# LED_Bar_Graph_Voltage_Display.net
KiCad netlist of a schematic drawn in Altium Designer
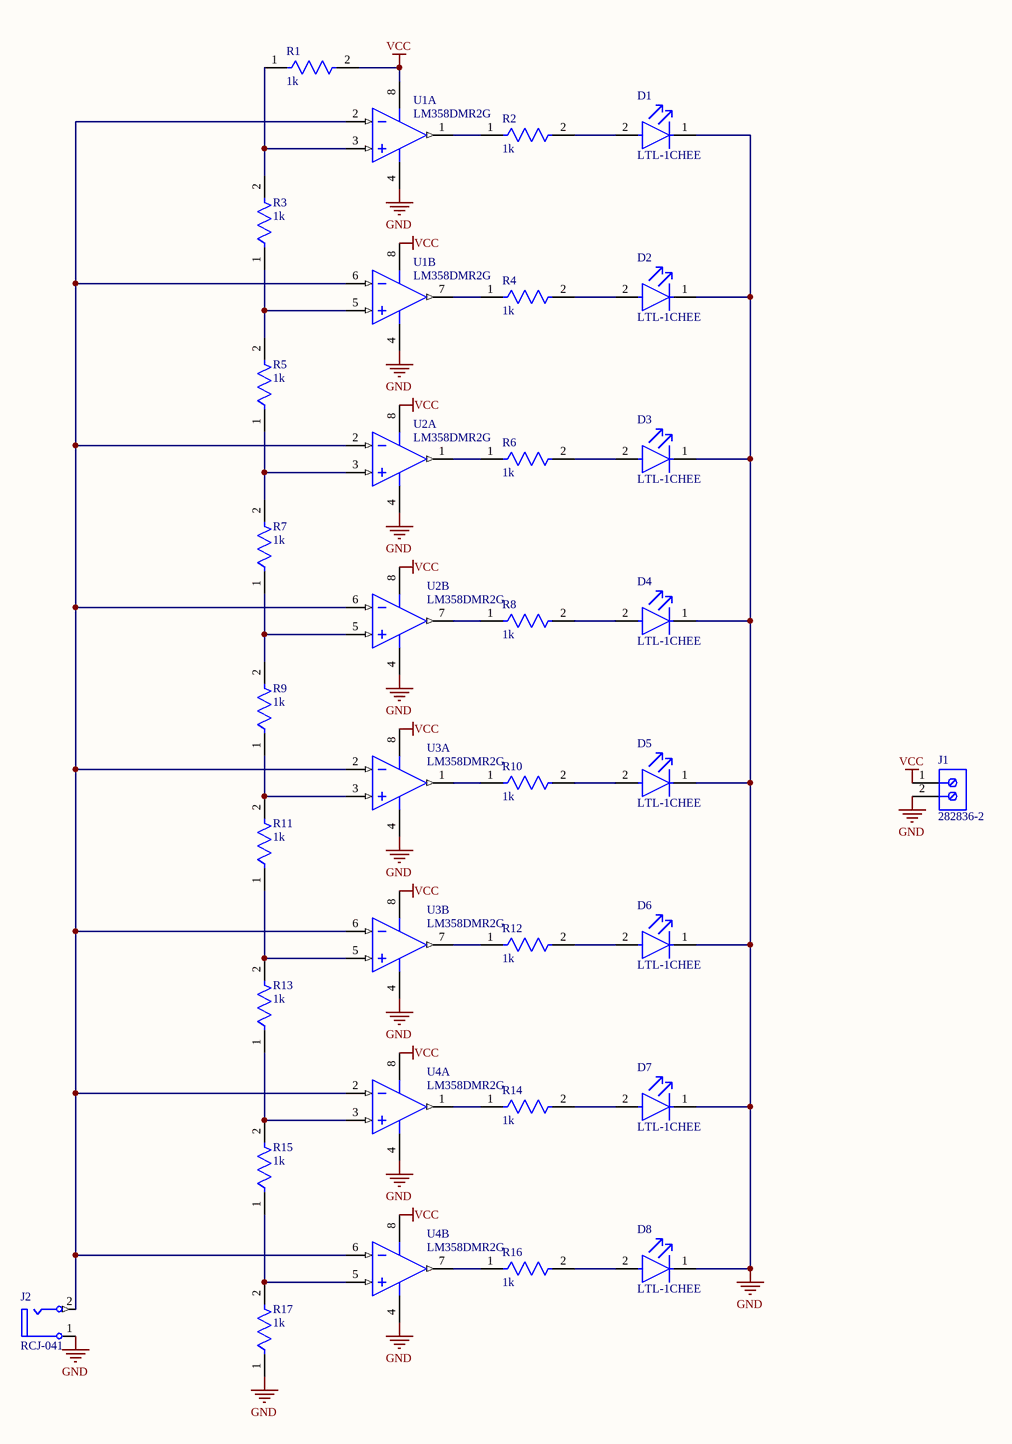
[diagram p0: LED Bar Graph Voltage Display.SchDoc]

(export (version "E")
  (design (tool "Eeschema 10.0.6"))
  (components
    (comp (ref "D1")
      (value "LTL-1CHEE")
      (footprint "FP-LTL-1CHEE-MFG")
      (description "LED RED CLEAR T/H")
      (libsource (lib "Altium Content Vault") (part "8706943c75ba83719d021d2fdc84c58"))
    )
    (comp (ref "D2")
      (value "LTL-1CHEE")
      (footprint "FP-LTL-1CHEE-MFG")
      (description "LED RED CLEAR T/H")
      (libsource (lib "Altium Content Vault") (part "8706943c75ba83719d021d2fdc84c58"))
    )
    (comp (ref "D3")
      (value "LTL-1CHEE")
      (footprint "FP-LTL-1CHEE-MFG")
      (description "LED RED CLEAR T/H")
      (libsource (lib "Altium Content Vault") (part "8706943c75ba83719d021d2fdc84c58"))
    )
    (comp (ref "D4")
      (value "LTL-1CHEE")
      (footprint "FP-LTL-1CHEE-MFG")
      (description "LED RED CLEAR T/H")
      (libsource (lib "Altium Content Vault") (part "8706943c75ba83719d021d2fdc84c58"))
    )
    (comp (ref "D5")
      (value "LTL-1CHEE")
      (footprint "FP-LTL-1CHEE-MFG")
      (description "LED RED CLEAR T/H")
      (libsource (lib "Altium Content Vault") (part "8706943c75ba83719d021d2fdc84c58"))
    )
    (comp (ref "D6")
      (value "LTL-1CHEE")
      (footprint "FP-LTL-1CHEE-MFG")
      (description "LED RED CLEAR T/H")
      (libsource (lib "Altium Content Vault") (part "8706943c75ba83719d021d2fdc84c58"))
    )
    (comp (ref "D7")
      (value "LTL-1CHEE")
      (footprint "FP-LTL-1CHEE-MFG")
      (description "LED RED CLEAR T/H")
      (libsource (lib "Altium Content Vault") (part "8706943c75ba83719d021d2fdc84c58"))
    )
    (comp (ref "D8")
      (value "LTL-1CHEE")
      (footprint "FP-LTL-1CHEE-MFG")
      (description "LED RED CLEAR T/H")
      (libsource (lib "Altium Content Vault") (part "8706943c75ba83719d021d2fdc84c58"))
    )
    (comp (ref "J1")
      (value "282836-2")
      (footprint "TECO-282836-2_V")
      (description "Female Header, Pitch 5 mm, 1 x 2 Position, Height 10 mm, Tail Length 3.5 mm, Rohs, Bulk")
      (fields (field (name "VOLTAGE") "300V") (field (name "MANUFACTURER") "TE Connectivity"))
      (libsource (lib "Altium Content Vault") (part "CN-1P-F-TB2"))
    )
    (comp (ref "J2")
      (value "RCJ-041")
      (footprint "CUI-RCJ-041_V")
      (description "Female RCJ Jack, 2 Position, Height 11.724 mm, Tail Length 4 mm, RoHS, Bulk")
      (libsource (lib "Altium Content Vault") (part "JACK-2CD2"))
    )
    (comp (ref "R1")
      (value "1k")
      (footprint "FP-CF14-MFG")
      (description "RES 7.5K OHM 1/4W 5% AXIAL")
      (fields (field (name "TOLERANCE") "5%"))
      (libsource (lib "Altium Content Vault") (part "1029c3af85768c4190bb7ad29bc67b5"))
    )
    (comp (ref "R2")
      (value "1k")
      (footprint "FP-CF14-MFG")
      (description "RES 7.5K OHM 1/4W 5% AXIAL")
      (fields (field (name "TOLERANCE") "5%"))
      (libsource (lib "Altium Content Vault") (part "1029c3af85768c4190bb7ad29bc67b5"))
    )
    (comp (ref "R3")
      (value "1k")
      (footprint "FP-CF14-MFG")
      (description "RES 7.5K OHM 1/4W 5% AXIAL")
      (fields (field (name "TOLERANCE") "5%"))
      (libsource (lib "Altium Content Vault") (part "1029c3af85768c4190bb7ad29bc67b5"))
    )
    (comp (ref "R4")
      (value "1k")
      (footprint "FP-CF14-MFG")
      (description "RES 7.5K OHM 1/4W 5% AXIAL")
      (fields (field (name "TOLERANCE") "5%"))
      (libsource (lib "Altium Content Vault") (part "1029c3af85768c4190bb7ad29bc67b5"))
    )
    (comp (ref "R5")
      (value "1k")
      (footprint "FP-CF14-MFG")
      (description "RES 7.5K OHM 1/4W 5% AXIAL")
      (fields (field (name "TOLERANCE") "5%"))
      (libsource (lib "Altium Content Vault") (part "1029c3af85768c4190bb7ad29bc67b5"))
    )
    (comp (ref "R6")
      (value "1k")
      (footprint "FP-CF14-MFG")
      (description "RES 7.5K OHM 1/4W 5% AXIAL")
      (fields (field (name "TOLERANCE") "5%"))
      (libsource (lib "Altium Content Vault") (part "1029c3af85768c4190bb7ad29bc67b5"))
    )
    (comp (ref "R7")
      (value "1k")
      (footprint "FP-CF14-MFG")
      (description "RES 7.5K OHM 1/4W 5% AXIAL")
      (fields (field (name "TOLERANCE") "5%"))
      (libsource (lib "Altium Content Vault") (part "1029c3af85768c4190bb7ad29bc67b5"))
    )
    (comp (ref "R8")
      (value "1k")
      (footprint "FP-CF14-MFG")
      (description "RES 7.5K OHM 1/4W 5% AXIAL")
      (fields (field (name "TOLERANCE") "5%"))
      (libsource (lib "Altium Content Vault") (part "1029c3af85768c4190bb7ad29bc67b5"))
    )
    (comp (ref "R9")
      (value "1k")
      (footprint "FP-CF14-MFG")
      (description "RES 7.5K OHM 1/4W 5% AXIAL")
      (fields (field (name "TOLERANCE") "5%"))
      (libsource (lib "Altium Content Vault") (part "1029c3af85768c4190bb7ad29bc67b5"))
    )
    (comp (ref "R10")
      (value "1k")
      (footprint "FP-CF14-MFG")
      (description "RES 7.5K OHM 1/4W 5% AXIAL")
      (fields (field (name "TOLERANCE") "5%"))
      (libsource (lib "Altium Content Vault") (part "1029c3af85768c4190bb7ad29bc67b5"))
    )
    (comp (ref "R11")
      (value "1k")
      (footprint "FP-CF14-MFG")
      (description "RES 7.5K OHM 1/4W 5% AXIAL")
      (fields (field (name "TOLERANCE") "5%"))
      (libsource (lib "Altium Content Vault") (part "1029c3af85768c4190bb7ad29bc67b5"))
    )
    (comp (ref "R12")
      (value "1k")
      (footprint "FP-CF14-MFG")
      (description "RES 7.5K OHM 1/4W 5% AXIAL")
      (fields (field (name "TOLERANCE") "5%"))
      (libsource (lib "Altium Content Vault") (part "1029c3af85768c4190bb7ad29bc67b5"))
    )
    (comp (ref "R13")
      (value "1k")
      (footprint "FP-CF14-MFG")
      (description "RES 7.5K OHM 1/4W 5% AXIAL")
      (fields (field (name "TOLERANCE") "5%"))
      (libsource (lib "Altium Content Vault") (part "1029c3af85768c4190bb7ad29bc67b5"))
    )
    (comp (ref "R14")
      (value "1k")
      (footprint "FP-CF14-MFG")
      (description "RES 7.5K OHM 1/4W 5% AXIAL")
      (fields (field (name "TOLERANCE") "5%"))
      (libsource (lib "Altium Content Vault") (part "1029c3af85768c4190bb7ad29bc67b5"))
    )
    (comp (ref "R15")
      (value "1k")
      (footprint "FP-CF14-MFG")
      (description "RES 7.5K OHM 1/4W 5% AXIAL")
      (fields (field (name "TOLERANCE") "5%"))
      (libsource (lib "Altium Content Vault") (part "1029c3af85768c4190bb7ad29bc67b5"))
    )
    (comp (ref "R16")
      (value "1k")
      (footprint "FP-CF14-MFG")
      (description "RES 7.5K OHM 1/4W 5% AXIAL")
      (fields (field (name "TOLERANCE") "5%"))
      (libsource (lib "Altium Content Vault") (part "1029c3af85768c4190bb7ad29bc67b5"))
    )
    (comp (ref "R17")
      (value "1k")
      (footprint "FP-CF14-MFG")
      (description "RES 7.5K OHM 1/4W 5% AXIAL")
      (fields (field (name "TOLERANCE") "5%"))
      (libsource (lib "Altium Content Vault") (part "1029c3af85768c4190bb7ad29bc67b5"))
    )
    (comp (ref "U1")
      (value "LM358DMR2G")
      (footprint "ONSC-MICRO-8-846A-02_H_V")
      (fields (field (name "MANUFACTURER") "On Semiconductor"))
      (libsource (lib "Altium Content Vault") (part "ONSC-LM358_NCV2904-8"))
    )
    (comp (ref "U2")
      (value "LM358DMR2G")
      (footprint "ONSC-MICRO-8-846A-02_H_V")
      (fields (field (name "MANUFACTURER") "On Semiconductor"))
      (libsource (lib "Altium Content Vault") (part "ONSC-LM358_NCV2904-8"))
    )
    (comp (ref "U3")
      (value "LM358DMR2G")
      (footprint "ONSC-MICRO-8-846A-02_H_V")
      (fields (field (name "MANUFACTURER") "On Semiconductor"))
      (libsource (lib "Altium Content Vault") (part "ONSC-LM358_NCV2904-8"))
    )
    (comp (ref "U4")
      (value "LM358DMR2G")
      (footprint "ONSC-MICRO-8-846A-02_H_V")
      (fields (field (name "MANUFACTURER") "On Semiconductor"))
      (libsource (lib "Altium Content Vault") (part "ONSC-LM358_NCV2904-8"))
    )
  )
  (nets
    (net (code "1") (name "GND") (class "Default")
      (node (ref "D1") (pin "1") (pinfunction "C_1") (pintype "passive"))
      (node (ref "D2") (pin "1") (pinfunction "C_1") (pintype "passive"))
      (node (ref "D3") (pin "1") (pinfunction "C_1") (pintype "passive"))
      (node (ref "D4") (pin "1") (pinfunction "C_1") (pintype "passive"))
      (node (ref "D5") (pin "1") (pinfunction "C_1") (pintype "passive"))
      (node (ref "D6") (pin "1") (pinfunction "C_1") (pintype "passive"))
      (node (ref "D7") (pin "1") (pinfunction "C_1") (pintype "passive"))
      (node (ref "D8") (pin "1") (pinfunction "C_1") (pintype "passive"))
      (node (ref "J1") (pin "2") (pinfunction "2_2") (pintype "passive"))
      (node (ref "J2") (pin "1") (pinfunction "1_1") (pintype "passive"))
      (node (ref "R17") (pin "1") (pinfunction "1_1") (pintype "passive"))
      (node (ref "U1") (pin "4") (pinfunction "VEE/GND_4") (pintype "power_in"))
      (node (ref "U2") (pin "4") (pinfunction "VEE/GND_4") (pintype "power_in"))
      (node (ref "U3") (pin "4") (pinfunction "VEE/GND_4") (pintype "power_in"))
      (node (ref "U4") (pin "4") (pinfunction "VEE/GND_4") (pintype "power_in"))
    )
    (net (code "2") (name "Net-(D1-A)") (class "Default")
      (node (ref "D1") (pin "2") (pinfunction "A_2") (pintype "passive"))
      (node (ref "R2") (pin "2") (pinfunction "2_2") (pintype "passive"))
    )
    (net (code "3") (name "Net-(D2-A)") (class "Default")
      (node (ref "D2") (pin "2") (pinfunction "A_2") (pintype "passive"))
      (node (ref "R4") (pin "2") (pinfunction "2_2") (pintype "passive"))
    )
    (net (code "4") (name "Net-(D3-A)") (class "Default")
      (node (ref "D3") (pin "2") (pinfunction "A_2") (pintype "passive"))
      (node (ref "R6") (pin "2") (pinfunction "2_2") (pintype "passive"))
    )
    (net (code "5") (name "Net-(D4-A)") (class "Default")
      (node (ref "D4") (pin "2") (pinfunction "A_2") (pintype "passive"))
      (node (ref "R8") (pin "2") (pinfunction "2_2") (pintype "passive"))
    )
    (net (code "6") (name "Net-(D5-A)") (class "Default")
      (node (ref "D5") (pin "2") (pinfunction "A_2") (pintype "passive"))
      (node (ref "R10") (pin "2") (pinfunction "2_2") (pintype "passive"))
    )
    (net (code "7") (name "Net-(D6-A)") (class "Default")
      (node (ref "D6") (pin "2") (pinfunction "A_2") (pintype "passive"))
      (node (ref "R12") (pin "2") (pinfunction "2_2") (pintype "passive"))
    )
    (net (code "8") (name "Net-(D7-A)") (class "Default")
      (node (ref "D7") (pin "2") (pinfunction "A_2") (pintype "passive"))
      (node (ref "R14") (pin "2") (pinfunction "2_2") (pintype "passive"))
    )
    (net (code "9") (name "Net-(D8-A)") (class "Default")
      (node (ref "D8") (pin "2") (pinfunction "A_2") (pintype "passive"))
      (node (ref "R16") (pin "2") (pinfunction "2_2") (pintype "passive"))
    )
    (net (code "10") (name "Net-(U1A-INA+)") (class "Default")
      (node (ref "R1") (pin "1") (pinfunction "1_1") (pintype "passive"))
      (node (ref "R3") (pin "2") (pinfunction "2_2") (pintype "passive"))
      (node (ref "U1") (pin "3") (pinfunction "INA+_3") (pintype "input"))
    )
    (net (code "11") (name "Net-(U1A-INA-)") (class "Default")
      (node (ref "J2") (pin "2") (pinfunction "2_2") (pintype "output"))
      (node (ref "U1") (pin "2") (pinfunction "INA-_2") (pintype "input"))
      (node (ref "U1") (pin "6") (pinfunction "INB-_6") (pintype "input"))
      (node (ref "U2") (pin "2") (pinfunction "INA-_2") (pintype "input"))
      (node (ref "U2") (pin "6") (pinfunction "INB-_6") (pintype "input"))
      (node (ref "U3") (pin "2") (pinfunction "INA-_2") (pintype "input"))
      (node (ref "U3") (pin "6") (pinfunction "INB-_6") (pintype "input"))
      (node (ref "U4") (pin "2") (pinfunction "INA-_2") (pintype "input"))
      (node (ref "U4") (pin "6") (pinfunction "INB-_6") (pintype "input"))
    )
    (net (code "12") (name "Net-(U1A-OUTA)") (class "Default")
      (node (ref "R2") (pin "1") (pinfunction "1_1") (pintype "passive"))
      (node (ref "U1") (pin "1") (pinfunction "OUTA_1") (pintype "output"))
    )
    (net (code "13") (name "Net-(U1B-INB+)") (class "Default")
      (node (ref "R3") (pin "1") (pinfunction "1_1") (pintype "passive"))
      (node (ref "R5") (pin "2") (pinfunction "2_2") (pintype "passive"))
      (node (ref "U1") (pin "5") (pinfunction "INB+_5") (pintype "input"))
    )
    (net (code "14") (name "Net-(U1B-OUTB)") (class "Default")
      (node (ref "R4") (pin "1") (pinfunction "1_1") (pintype "passive"))
      (node (ref "U1") (pin "7") (pinfunction "OUTB_7") (pintype "output"))
    )
    (net (code "15") (name "Net-(U2A-INA+)") (class "Default")
      (node (ref "R5") (pin "1") (pinfunction "1_1") (pintype "passive"))
      (node (ref "R7") (pin "2") (pinfunction "2_2") (pintype "passive"))
      (node (ref "U2") (pin "3") (pinfunction "INA+_3") (pintype "input"))
    )
    (net (code "16") (name "Net-(U2A-OUTA)") (class "Default")
      (node (ref "R6") (pin "1") (pinfunction "1_1") (pintype "passive"))
      (node (ref "U2") (pin "1") (pinfunction "OUTA_1") (pintype "output"))
    )
    (net (code "17") (name "Net-(U2B-INB+)") (class "Default")
      (node (ref "R7") (pin "1") (pinfunction "1_1") (pintype "passive"))
      (node (ref "R9") (pin "2") (pinfunction "2_2") (pintype "passive"))
      (node (ref "U2") (pin "5") (pinfunction "INB+_5") (pintype "input"))
    )
    (net (code "18") (name "Net-(U2B-OUTB)") (class "Default")
      (node (ref "R8") (pin "1") (pinfunction "1_1") (pintype "passive"))
      (node (ref "U2") (pin "7") (pinfunction "OUTB_7") (pintype "output"))
    )
    (net (code "19") (name "Net-(U3A-INA+)") (class "Default")
      (node (ref "R11") (pin "2") (pinfunction "2_2") (pintype "passive"))
      (node (ref "R9") (pin "1") (pinfunction "1_1") (pintype "passive"))
      (node (ref "U3") (pin "3") (pinfunction "INA+_3") (pintype "input"))
    )
    (net (code "20") (name "Net-(U3A-OUTA)") (class "Default")
      (node (ref "R10") (pin "1") (pinfunction "1_1") (pintype "passive"))
      (node (ref "U3") (pin "1") (pinfunction "OUTA_1") (pintype "output"))
    )
    (net (code "21") (name "Net-(U3B-INB+)") (class "Default")
      (node (ref "R11") (pin "1") (pinfunction "1_1") (pintype "passive"))
      (node (ref "R13") (pin "2") (pinfunction "2_2") (pintype "passive"))
      (node (ref "U3") (pin "5") (pinfunction "INB+_5") (pintype "input"))
    )
    (net (code "22") (name "Net-(U3B-OUTB)") (class "Default")
      (node (ref "R12") (pin "1") (pinfunction "1_1") (pintype "passive"))
      (node (ref "U3") (pin "7") (pinfunction "OUTB_7") (pintype "output"))
    )
    (net (code "23") (name "Net-(U4A-INA+)") (class "Default")
      (node (ref "R13") (pin "1") (pinfunction "1_1") (pintype "passive"))
      (node (ref "R15") (pin "2") (pinfunction "2_2") (pintype "passive"))
      (node (ref "U4") (pin "3") (pinfunction "INA+_3") (pintype "input"))
    )
    (net (code "24") (name "Net-(U4A-OUTA)") (class "Default")
      (node (ref "R14") (pin "1") (pinfunction "1_1") (pintype "passive"))
      (node (ref "U4") (pin "1") (pinfunction "OUTA_1") (pintype "output"))
    )
    (net (code "25") (name "Net-(U4B-INB+)") (class "Default")
      (node (ref "R15") (pin "1") (pinfunction "1_1") (pintype "passive"))
      (node (ref "R17") (pin "2") (pinfunction "2_2") (pintype "passive"))
      (node (ref "U4") (pin "5") (pinfunction "INB+_5") (pintype "input"))
    )
    (net (code "26") (name "Net-(U4B-OUTB)") (class "Default")
      (node (ref "R16") (pin "1") (pinfunction "1_1") (pintype "passive"))
      (node (ref "U4") (pin "7") (pinfunction "OUTB_7") (pintype "output"))
    )
    (net (code "27") (name "VCC") (class "Default")
      (node (ref "J1") (pin "1") (pinfunction "1_1") (pintype "passive"))
      (node (ref "R1") (pin "2") (pinfunction "2_2") (pintype "passive"))
      (node (ref "U1") (pin "8") (pinfunction "VCC_8") (pintype "power_in"))
      (node (ref "U2") (pin "8") (pinfunction "VCC_8") (pintype "power_in"))
      (node (ref "U3") (pin "8") (pinfunction "VCC_8") (pintype "power_in"))
      (node (ref "U4") (pin "8") (pinfunction "VCC_8") (pintype "power_in"))
    )
  )
)
